# DualEncoderBoard-v2_0.net
KiCad netlist of a schematic drawn in EAGLE
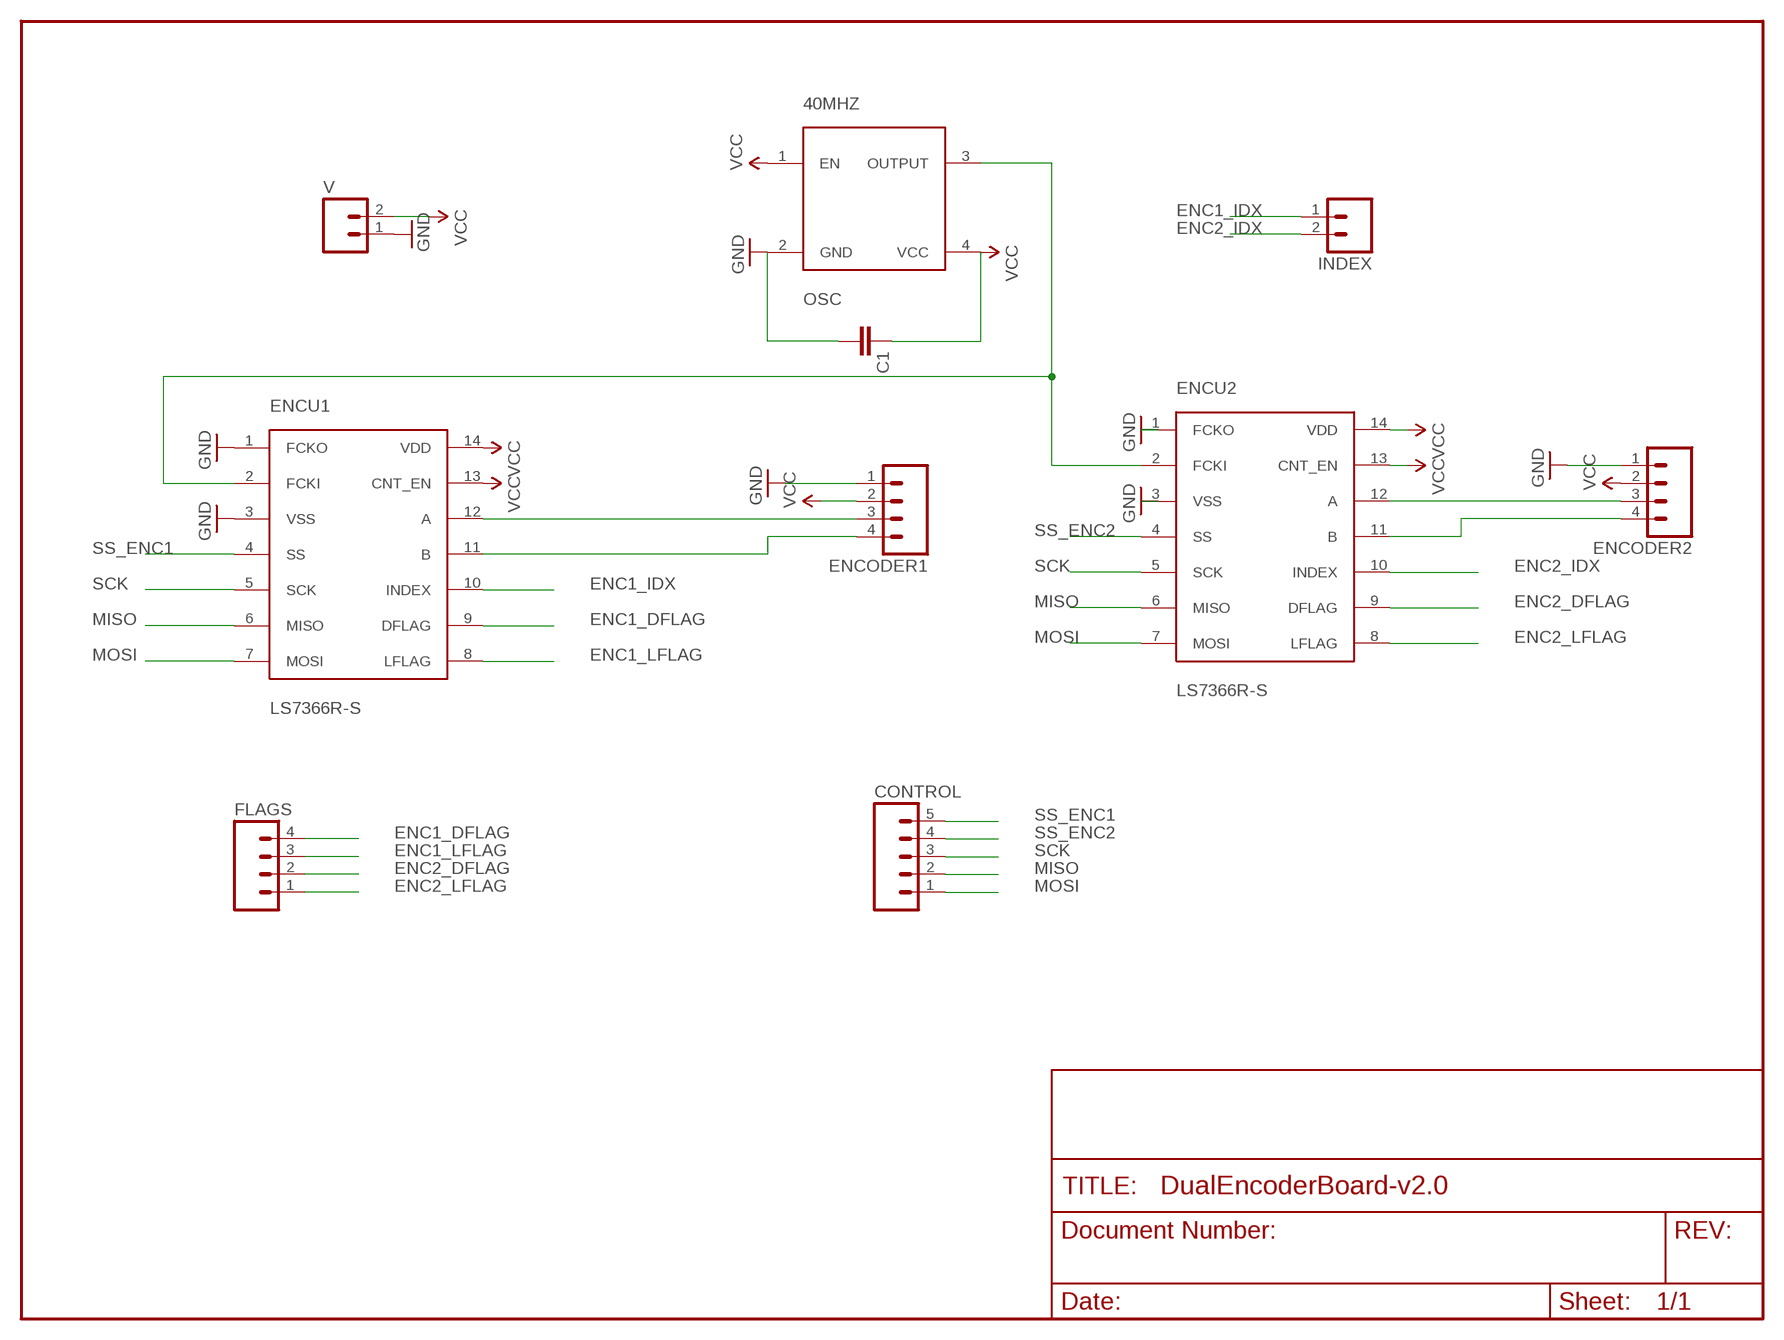
[diagram p0: schematic, sheet 1]

(export (version "E")
  (design (tool "Eeschema 10.0.6"))
  (components
    (comp (ref "40MHZ")
      (value "OSC")
      (footprint "eagle-import:CB3OSCILLATOR")
      (libsource (lib "eagle-import") (part "OSC"))
    )
    (comp (ref "C1")
      (value "CAPKIT")
      (footprint "eagle-import:CAP-PTH-SMALL-KIT")
      (libsource (lib "eagle-import") (part "CAPKIT"))
    )
    (comp (ref "CONTROL")
      (value "M05PTH")
      (footprint "eagle-import:1X05")
      (libsource (lib "eagle-import") (part "M05PTH"))
    )
    (comp (ref "ENCODER1")
      (value "M04POLAR")
      (footprint "eagle-import:MOLEX-1X4")
      (libsource (lib "eagle-import") (part "M04POLAR"))
    )
    (comp (ref "ENCODER2")
      (value "M04POLAR")
      (footprint "eagle-import:MOLEX-1X4")
      (libsource (lib "eagle-import") (part "M04POLAR"))
    )
    (comp (ref "ENCU1")
      (value "LS7366R-S")
      (footprint "eagle-import:SO14")
      (libsource (lib "eagle-import") (part "LS7366R-S"))
    )
    (comp (ref "ENCU2")
      (value "LS7366R-S")
      (footprint "eagle-import:SO14")
      (libsource (lib "eagle-import") (part "LS7366R-S"))
    )
    (comp (ref "FLAGS")
      (value "M04PTH")
      (footprint "eagle-import:1X04")
      (libsource (lib "eagle-import") (part "M04PTH"))
    )
    (comp (ref "INDEX")
      (value "M02PTH")
      (footprint "eagle-import:1X02")
      (libsource (lib "eagle-import") (part "M02PTH"))
    )
    (comp (ref "V")
      (value "M02-JST-2MM-SMT")
      (footprint "eagle-import:JST-2-SMD")
      (libsource (lib "eagle-import") (part "M02-JST-2MM-SMT"))
    )
  )
  (nets
    (net (code "1") (name "/ENC1_DFLAG") (class "Default")
      (node (ref "ENCU1") (pin "9") (pinfunction "DFLAG_9") (pintype "output"))
      (node (ref "FLAGS") (pin "4") (pinfunction "4_4") (pintype "passive"))
    )
    (net (code "2") (name "/ENC1_IDX") (class "Default")
      (node (ref "ENCU1") (pin "10") (pinfunction "INDEX_10") (pintype "input"))
      (node (ref "INDEX") (pin "1") (pinfunction "1_1") (pintype "passive"))
    )
    (net (code "3") (name "/ENC1_LFLAG") (class "Default")
      (node (ref "ENCU1") (pin "8") (pinfunction "LFLAG_8") (pintype "output"))
      (node (ref "FLAGS") (pin "3") (pinfunction "3_3") (pintype "passive"))
    )
    (net (code "4") (name "/ENC2_DFLAG") (class "Default")
      (node (ref "ENCU2") (pin "9") (pinfunction "DFLAG_9") (pintype "output"))
      (node (ref "FLAGS") (pin "2") (pinfunction "2_2") (pintype "passive"))
    )
    (net (code "5") (name "/ENC2_IDX") (class "Default")
      (node (ref "ENCU2") (pin "10") (pinfunction "INDEX_10") (pintype "input"))
      (node (ref "INDEX") (pin "2") (pinfunction "2_2") (pintype "passive"))
    )
    (net (code "6") (name "/ENC2_LFLAG") (class "Default")
      (node (ref "ENCU2") (pin "8") (pinfunction "LFLAG_8") (pintype "output"))
      (node (ref "FLAGS") (pin "1") (pinfunction "1_1") (pintype "passive"))
    )
    (net (code "7") (name "/MISO") (class "Default")
      (node (ref "CONTROL") (pin "2") (pinfunction "2_2") (pintype "passive"))
      (node (ref "ENCU1") (pin "6") (pinfunction "MISO_6") (pintype "output"))
      (node (ref "ENCU2") (pin "6") (pinfunction "MISO_6") (pintype "output"))
    )
    (net (code "8") (name "/MOSI") (class "Default")
      (node (ref "CONTROL") (pin "1") (pinfunction "1_1") (pintype "passive"))
      (node (ref "ENCU1") (pin "7") (pinfunction "MOSI_7") (pintype "input"))
      (node (ref "ENCU2") (pin "7") (pinfunction "MOSI_7") (pintype "input"))
    )
    (net (code "9") (name "/SCK") (class "Default")
      (node (ref "CONTROL") (pin "3") (pinfunction "3_3") (pintype "passive"))
      (node (ref "ENCU1") (pin "5") (pinfunction "SCK_5") (pintype "input"))
      (node (ref "ENCU2") (pin "5") (pinfunction "SCK_5") (pintype "input"))
    )
    (net (code "10") (name "/SS_ENC1") (class "Default")
      (node (ref "CONTROL") (pin "5") (pinfunction "5_5") (pintype "passive"))
      (node (ref "ENCU1") (pin "4") (pinfunction "SS_4") (pintype "input"))
    )
    (net (code "11") (name "/SS_ENC2") (class "Default")
      (node (ref "CONTROL") (pin "4") (pinfunction "4_4") (pintype "passive"))
      (node (ref "ENCU2") (pin "4") (pinfunction "SS_4") (pintype "input"))
    )
    (net (code "12") (name "GND") (class "Default")
      (node (ref "40MHZ") (pin "2") (pinfunction "GND_2") (pintype "input"))
      (node (ref "C1") (pin "2") (pinfunction "2_2") (pintype "passive"))
      (node (ref "ENCODER1") (pin "1") (pinfunction "1_1") (pintype "passive"))
      (node (ref "ENCODER2") (pin "1") (pinfunction "1_1") (pintype "passive"))
      (node (ref "ENCU1") (pin "1") (pinfunction "FCKO_1") (pintype "output"))
      (node (ref "ENCU1") (pin "3") (pinfunction "VSS_3") (pintype "power_in"))
      (node (ref "ENCU2") (pin "1") (pinfunction "FCKO_1") (pintype "output"))
      (node (ref "ENCU2") (pin "3") (pinfunction "VSS_3") (pintype "power_in"))
      (node (ref "V") (pin "1") (pinfunction "1_1") (pintype "passive"))
    )
    (net (code "13") (name "Net-(40MHZ-OUTPUT)") (class "Default")
      (node (ref "40MHZ") (pin "3") (pinfunction "OUTPUT_3") (pintype "output"))
      (node (ref "ENCU1") (pin "2") (pinfunction "FCKI_2") (pintype "input"))
      (node (ref "ENCU2") (pin "2") (pinfunction "FCKI_2") (pintype "input"))
    )
    (net (code "14") (name "Net-(ENCU1-A)") (class "Default")
      (node (ref "ENCODER1") (pin "3") (pinfunction "3_3") (pintype "passive"))
      (node (ref "ENCU1") (pin "12") (pinfunction "A_12") (pintype "input"))
    )
    (net (code "15") (name "Net-(ENCU1-B)") (class "Default")
      (node (ref "ENCODER1") (pin "4") (pinfunction "4_4") (pintype "passive"))
      (node (ref "ENCU1") (pin "11") (pinfunction "B_11") (pintype "input"))
    )
    (net (code "16") (name "Net-(ENCU2-A)") (class "Default")
      (node (ref "ENCODER2") (pin "3") (pinfunction "3_3") (pintype "passive"))
      (node (ref "ENCU2") (pin "12") (pinfunction "A_12") (pintype "input"))
    )
    (net (code "17") (name "Net-(ENCU2-B)") (class "Default")
      (node (ref "ENCODER2") (pin "4") (pinfunction "4_4") (pintype "passive"))
      (node (ref "ENCU2") (pin "11") (pinfunction "B_11") (pintype "input"))
    )
    (net (code "18") (name "VCC") (class "Default")
      (node (ref "40MHZ") (pin "1") (pinfunction "EN_1") (pintype "input"))
      (node (ref "40MHZ") (pin "4") (pinfunction "VCC_4") (pintype "input"))
      (node (ref "C1") (pin "1") (pinfunction "1_1") (pintype "passive"))
      (node (ref "ENCODER1") (pin "2") (pinfunction "2_2") (pintype "passive"))
      (node (ref "ENCODER2") (pin "2") (pinfunction "2_2") (pintype "passive"))
      (node (ref "ENCU1") (pin "13") (pinfunction "CNT_EN_13") (pintype "input"))
      (node (ref "ENCU1") (pin "14") (pinfunction "VDD_14") (pintype "power_in"))
      (node (ref "ENCU2") (pin "13") (pinfunction "CNT_EN_13") (pintype "input"))
      (node (ref "ENCU2") (pin "14") (pinfunction "VDD_14") (pintype "power_in"))
      (node (ref "V") (pin "2") (pinfunction "2_2") (pintype "passive"))
    )
  )
)
